# Main.net
KiCad netlist of a schematic drawn in Altium Designer
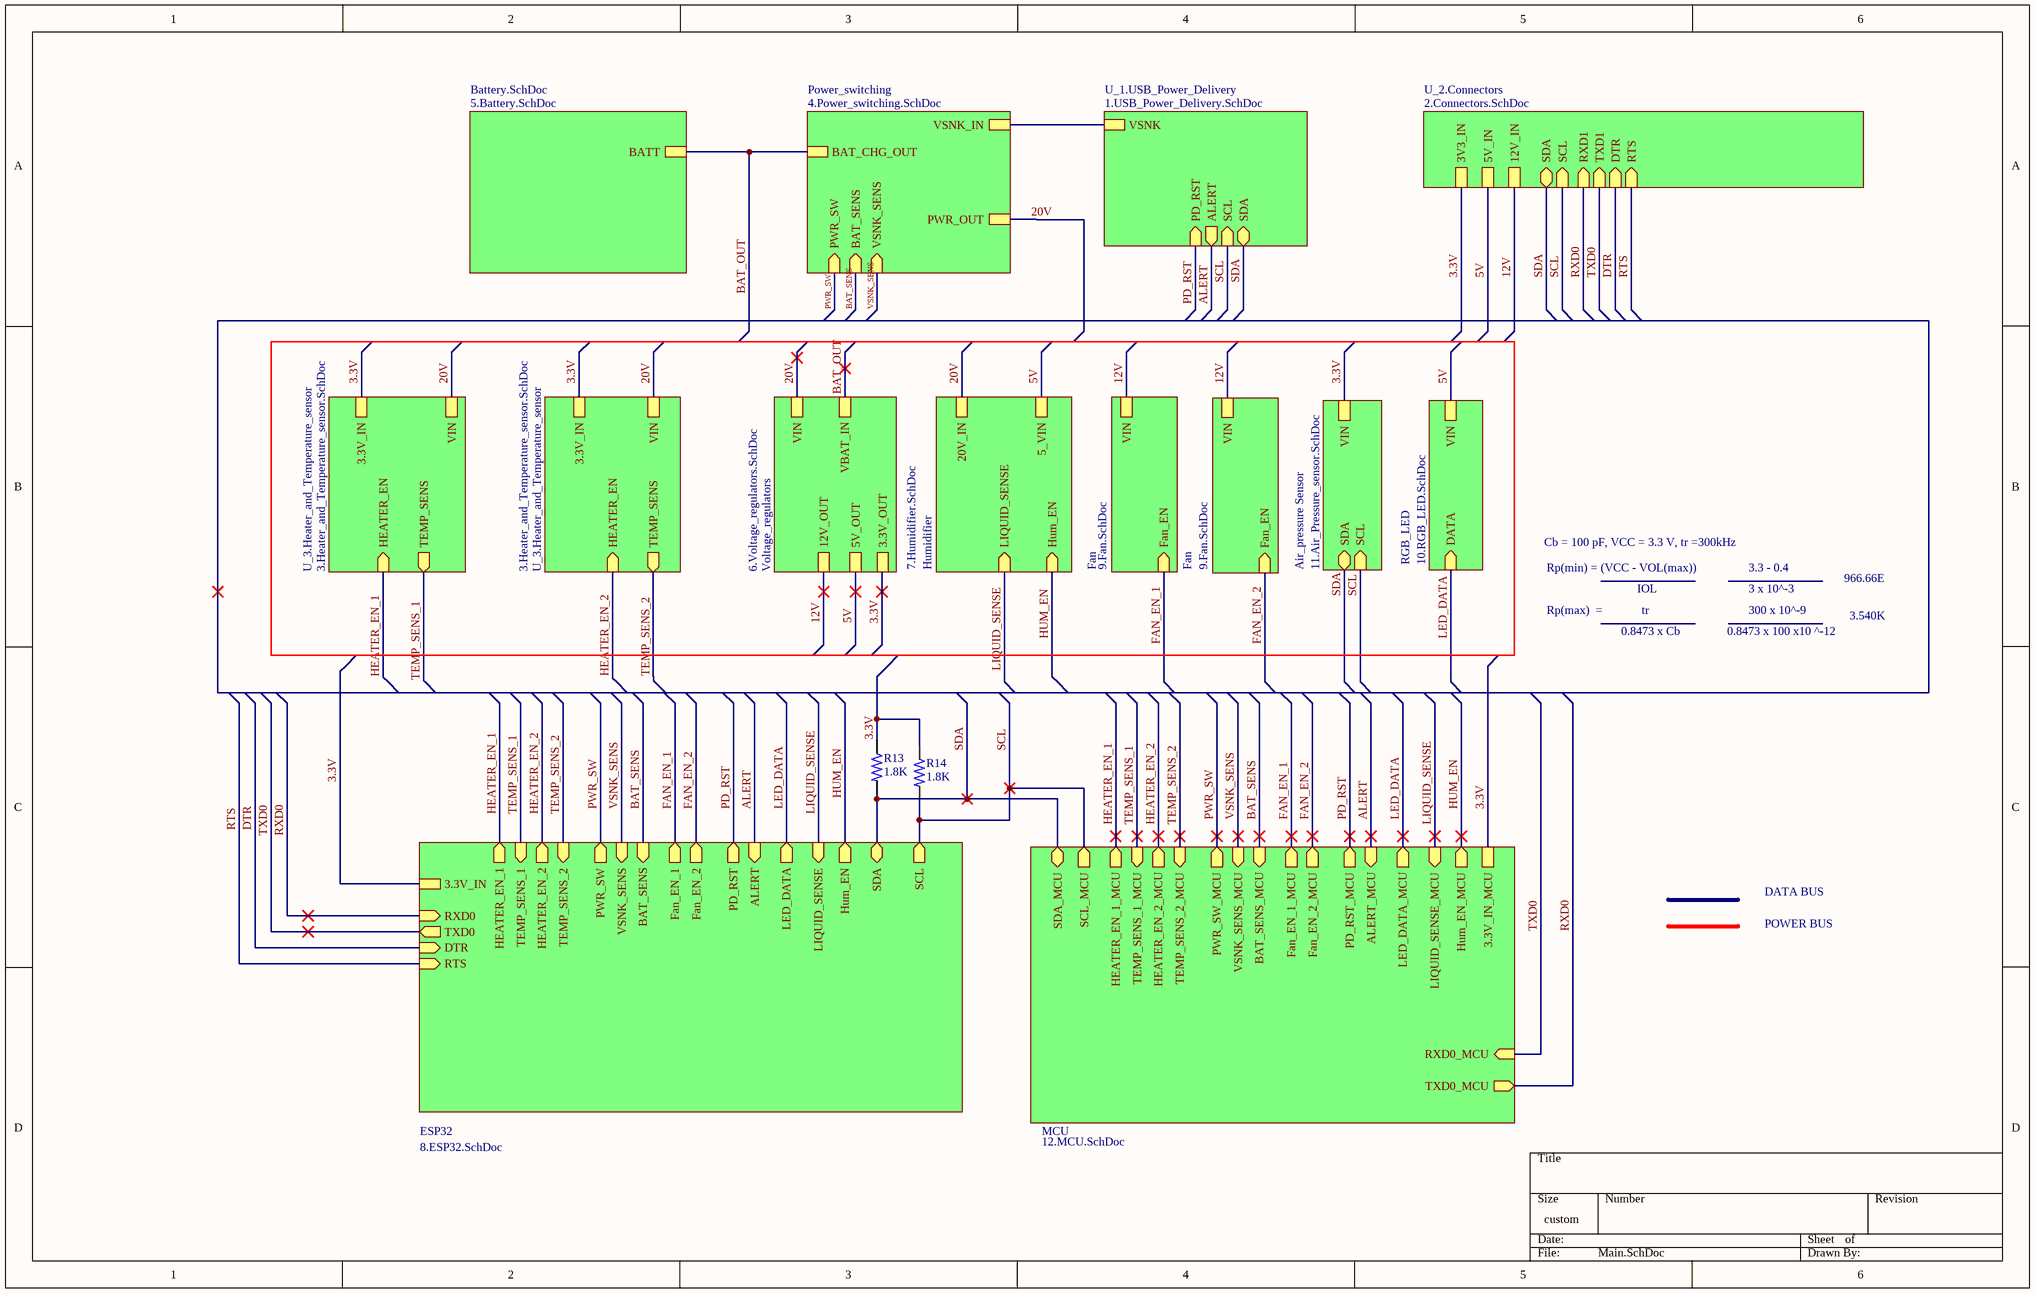
[diagram p0: Main.SchDoc]

(export (version "E")
  (design (tool "Eeschema 10.0.6"))
  (components
    (comp (ref "R13") (value "1.8K") (footprint "R_0603") (libsource (lib "Schlib") (part "R_0603")))
    (comp (ref "R14") (value "1.8K") (footprint "R_0603") (libsource (lib "Schlib") (part "R_0603")))
  )
  (nets
    (net (code "1") (name "/3.3V") (class "Default")
      (node (ref "R13") (pin "1") (pinfunction "1_1") (pintype "passive"))
      (node (ref "R14") (pin "1") (pinfunction "1_1") (pintype "passive"))
    )
    (net (code "22") (name "/SCL") (class "Default")
      (node (ref "R14") (pin "2") (pinfunction "2_2") (pintype "passive+no_connect"))
    )
    (net (code "24") (name "/SDA") (class "Default")
      (node (ref "R13") (pin "2") (pinfunction "2_2") (pintype "passive+no_connect"))
    )
  )
)
